# SCH_ELECTROSCOPE_2025-04-18.net
KiCad netlist of a schematic drawn in EasyEDA
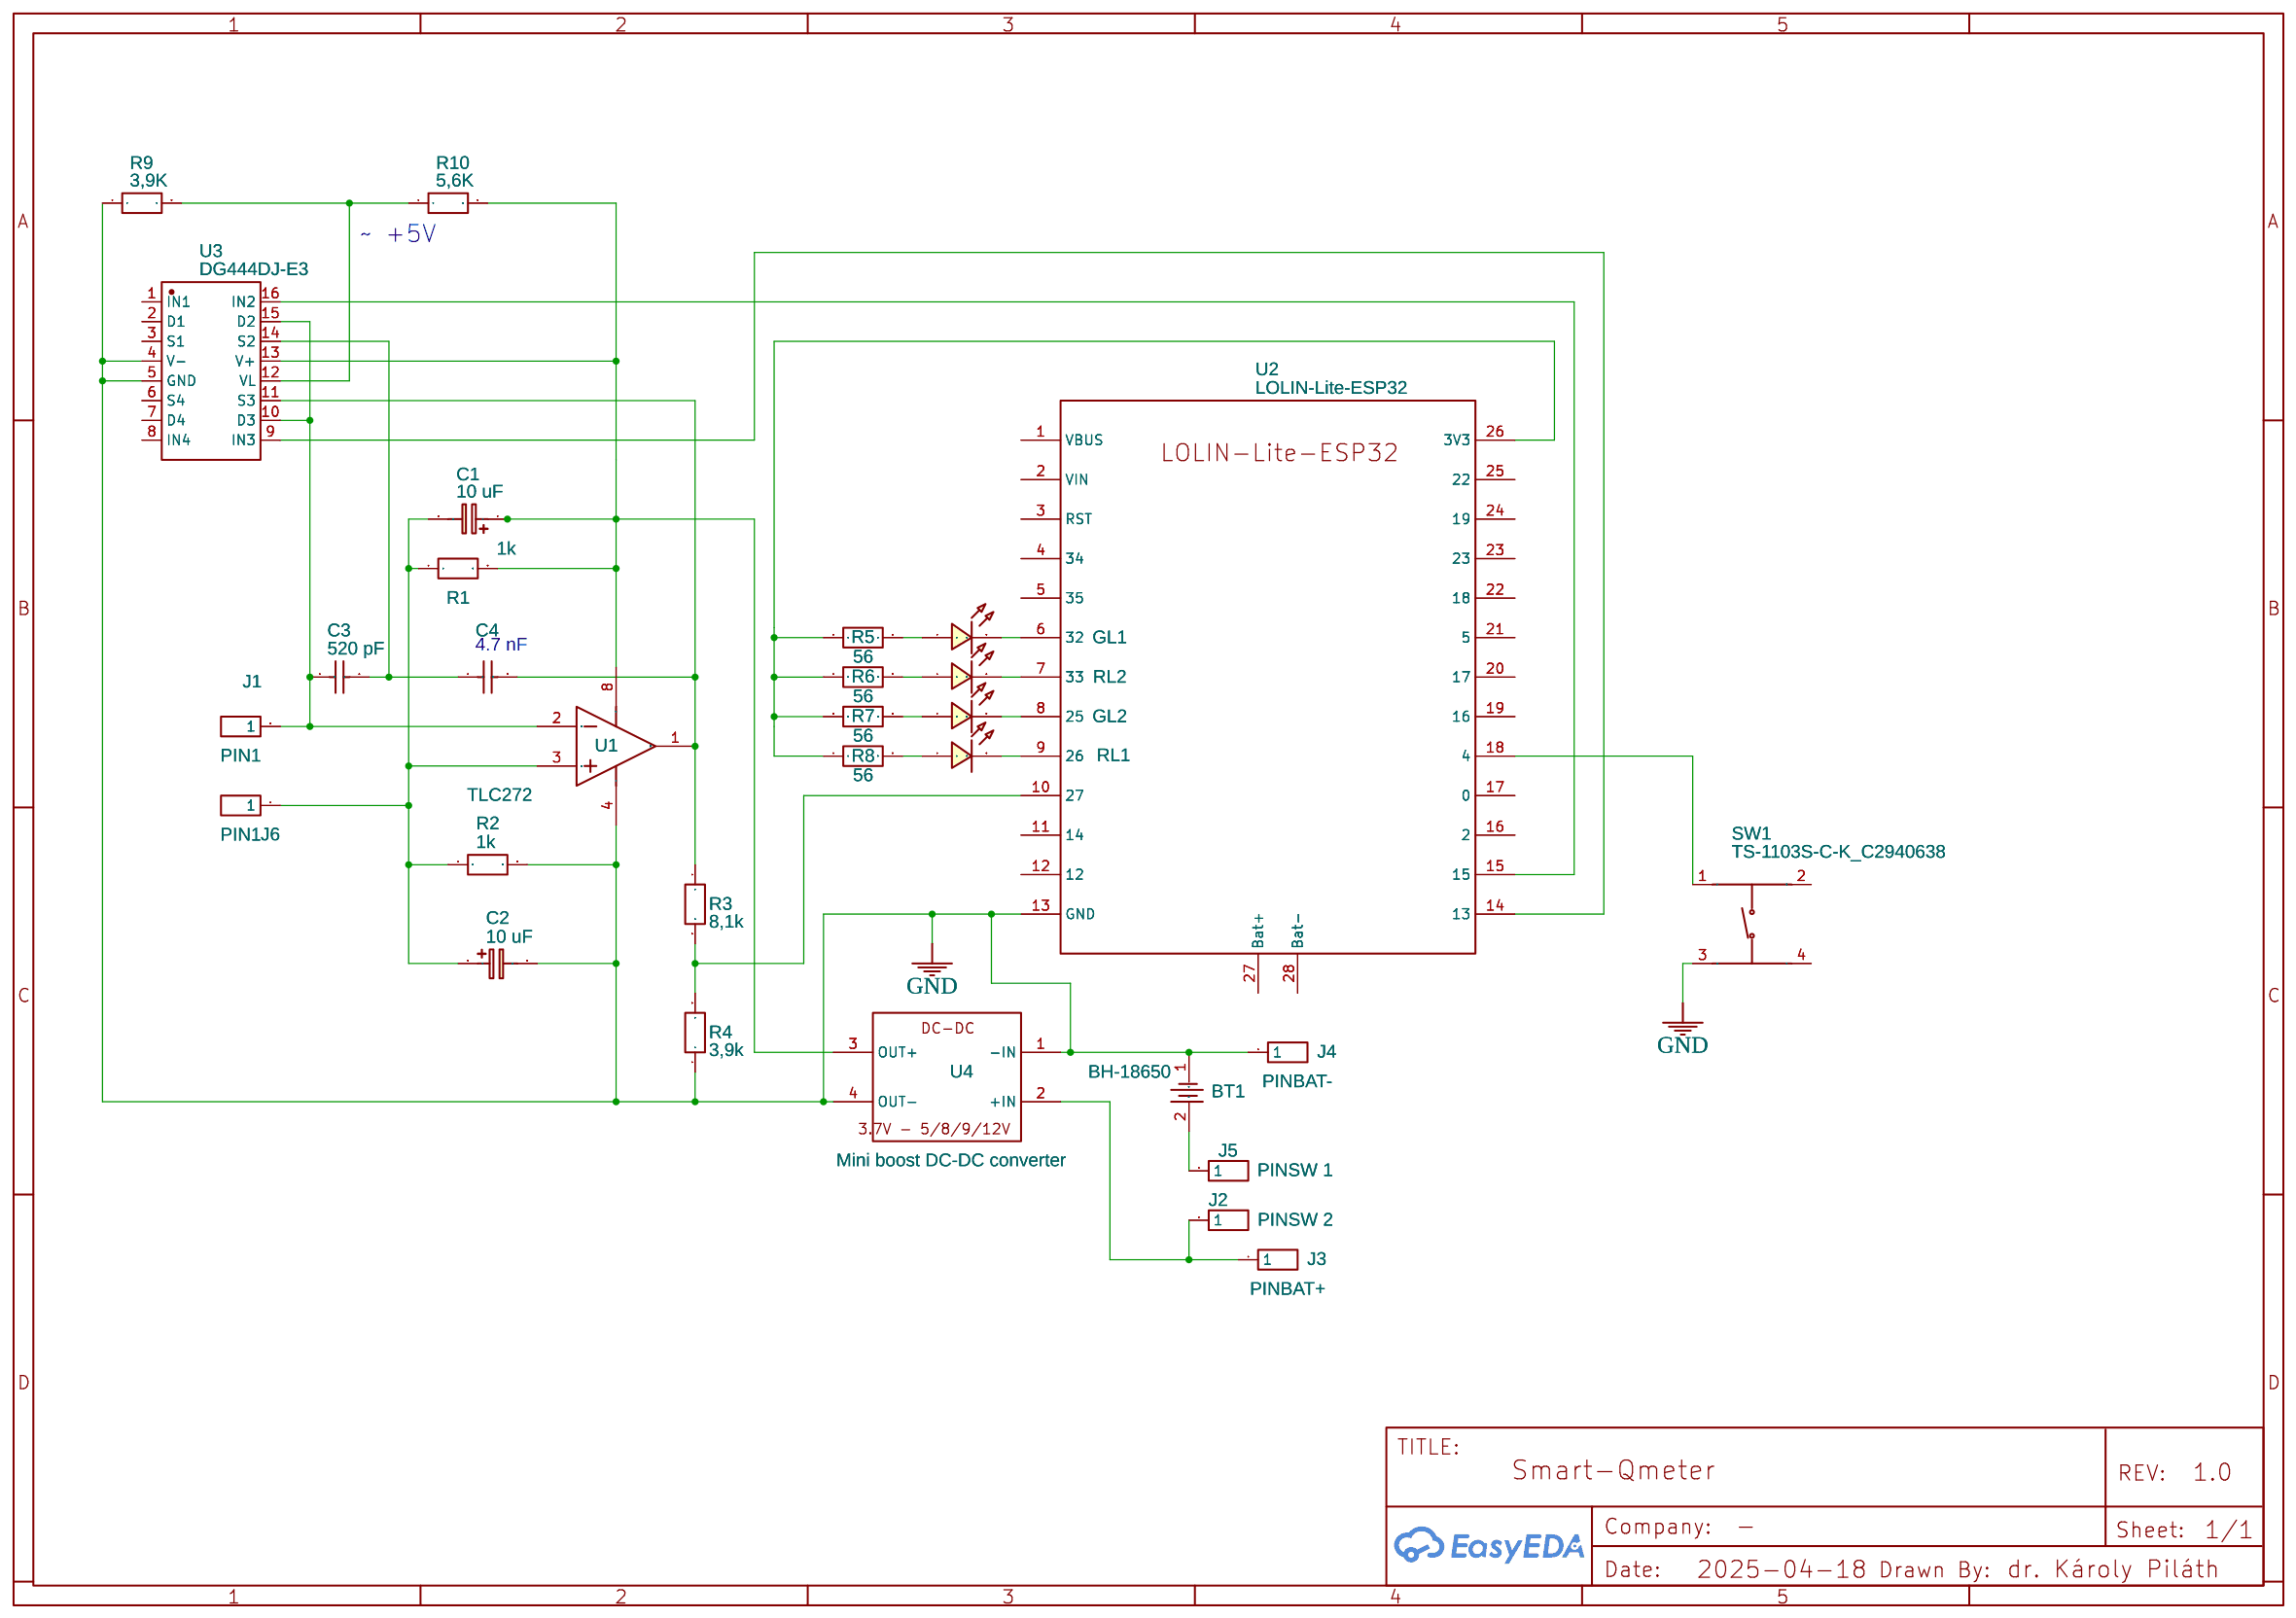
[diagram p0: schematic sheet]

(export (version "E")
  (design (tool "Eeschema 10.0.6"))
  (components
    (comp (ref "BT1")
      (value "BH-18650")
      (fields
        (field (name "Manufacturer Part") "BH-18650-B1BA002")
        (field (name "Manufacturer") "MYOUNG(美阳)")
      )
      (libsource (lib "") (part "BH-18650-B1BA002"))
    )
    (comp (ref "C1") (value "10 uF") (libsource (lib "") (part "CE_TH_D4.0×F1.5_EU")))
    (comp (ref "C2") (value "10 uF") (libsource (lib "") (part "CE_TH_D4.0×F1.5_EU_1")))
    (comp (ref "C3")
      (value "520 pF")
      (fields (field (name "Manufacturer Part") "Capacitor15nf100v") (field (name "Manufacturer") "ReliaPro"))
      (libsource (lib "") (part "CAPACITOR15NF100V"))
    )
    (comp (ref "C4")
      (value "10 nF")
      (fields (field (name "Manufacturer Part") "Capacitor15nf100v") (field (name "Manufacturer") "ReliaPro"))
      (libsource (lib "") (part "CAPACITOR15NF100V"))
    )
    (comp (ref "GL1")
      (value "LED-TH-5mm_R")
      (fields
        (field (name "Manufacturer Part") "333-2SURD/S530-A3")
        (field (name "Manufacturer") "EVERLIGHT(台湾亿光)")
      )
      (libsource (lib "") (part "LED-TH-5mm_R"))
    )
    (comp (ref "GL2")
      (value "LED-TH-5mm_R")
      (fields
        (field (name "Manufacturer Part") "333-2SURD/S530-A3")
        (field (name "Manufacturer") "EVERLIGHT(台湾亿光)")
      )
      (libsource (lib "") (part "LED-TH-5mm_R"))
    )
    (comp (ref "J1") (value "PIN1") (libsource (lib "") (part "HDR-M-2.54_1x1_1")))
    (comp (ref "J2") (value "PINSW 2") (libsource (lib "") (part "HDR-M-2.54_1x1")))
    (comp (ref "J3") (value "PINBAT+") (libsource (lib "") (part "HDR-M-2.54_1x1")))
    (comp (ref "J4") (value "PINBAT-") (libsource (lib "") (part "HDR-M-2.54_1x1")))
    (comp (ref "J5") (value "PINSW 1") (libsource (lib "") (part "HDR-M-2.54_1x1")))
    (comp (ref "J6") (value "PIN1") (libsource (lib "") (part "HDR-M-2.54_1x1_1")))
    (comp (ref "R1") (value "1k") (libsource (lib "") (part "R_AXIAL-0.4_EU")))
    (comp (ref "R2") (value "1k") (libsource (lib "") (part "R_AXIAL-0.4_EU")))
    (comp (ref "R3") (value "8,1k") (libsource (lib "") (part "R_AXIAL-0.4_EU_1")))
    (comp (ref "R4") (value "3,9k") (libsource (lib "") (part "R_AXIAL-0.4_EU_2")))
    (comp (ref "R5") (value "56") (libsource (lib "") (part "R_AXIAL-0.4_EU")))
    (comp (ref "R6") (value "56") (libsource (lib "") (part "R_AXIAL-0.4_EU")))
    (comp (ref "R7") (value "56") (libsource (lib "") (part "R_AXIAL-0.4_EU")))
    (comp (ref "R8") (value "56") (libsource (lib "") (part "R_AXIAL-0.4_EU")))
    (comp (ref "R9") (value "3,9K") (libsource (lib "") (part "R_AXIAL-0.4_EU")))
    (comp (ref "R10") (value "5,6K") (libsource (lib "") (part "R_AXIAL-0.4_EU")))
    (comp (ref "RL1")
      (value "LED-TH-5mm_R")
      (fields
        (field (name "Manufacturer Part") "333-2SURD/S530-A3")
        (field (name "Manufacturer") "EVERLIGHT(台湾亿光)")
      )
      (libsource (lib "") (part "LED-TH-5mm_R_1"))
    )
    (comp (ref "RL2")
      (value "LED-TH-5mm_R")
      (fields
        (field (name "Manufacturer Part") "333-2SURD/S530-A3")
        (field (name "Manufacturer") "EVERLIGHT(台湾亿光)")
      )
      (libsource (lib "") (part "LED-TH-5mm_R_1"))
    )
    (comp (ref "SW1")
      (value "TS-1103S-C-K_C2940638")
      (fields
        (field (name "Manufacturer Part") "TS-1103S-C-K")
        (field (name "Manufacturer") "XKB Connectivity(中国星坤)")
      )
      (libsource (lib "") (part "TS-1103S-C-K_C2940638"))
    )
    (comp (ref "U1")
      (value "TLC272")
      (fields (field (name "Manufacturer Part") "TL062CPE4") (field (name "Manufacturer") "TI(德州仪器)"))
      (libsource (lib "") (part "TL062CPE4"))
    )
    (comp (ref "U2")
      (value "LOLIN-Lite-ESP32")
      (fields (field (name "Manufacturer") "Wemos"))
      (libsource (lib "") (part "LOLIN-Lite-ESP32"))
    )
    (comp (ref "U3")
      (value "DG444DJ-E3")
      (fields (field (name "Manufacturer") "VISHAY(威世)"))
      (libsource (lib "") (part "DG444DJ-E3"))
    )
    (comp (ref "U4")
      (value "Mini boost DC-DC converter")
      (libsource (lib "") (part "Mini boost DC-DC converter"))
    )
  )
  (nets
    (net (code "1") (name "GND") (class "Default")
      (node (ref "BT1") (pin "1") (pinfunction "1_1") (pintype "input"))
      (node (ref "C2") (pin "2") (pinfunction "2_2") (pintype "unspecified"))
      (node (ref "J4") (pin "1") (pinfunction "1_1") (pintype "input"))
      (node (ref "R2") (pin "2") (pinfunction "2_2") (pintype "unspecified"))
      (node (ref "R4") (pin "1") (pinfunction "1_1") (pintype "unspecified"))
      (node (ref "R9") (pin "1") (pinfunction "1_1") (pintype "unspecified"))
      (node (ref "SW1") (pin "3") (pinfunction "3_3") (pintype "unspecified"))
      (node (ref "U1") (pin "4") (pinfunction "V-_4") (pintype "passive"))
      (node (ref "U2") (pin "13") (pinfunction "GND_13") (pintype "unspecified"))
      (node (ref "U3") (pin "4") (pinfunction "V-_4") (pintype "unspecified"))
      (node (ref "U3") (pin "5") (pinfunction "GND_5") (pintype "unspecified"))
      (node (ref "U4") (pin "1") (pinfunction "-IN_1") (pintype "unspecified"))
      (node (ref "U4") (pin "4") (pinfunction "OUT-_4") (pintype "unspecified"))
    )
    (net (code "2") (name "Net-(BT1-Pad2)") (class "Default")
      (node (ref "BT1") (pin "2") (pinfunction "2_2") (pintype "input"))
      (node (ref "J5") (pin "1") (pinfunction "1_1") (pintype "input"))
    )
    (net (code "3") (name "Net-(GL1-Pad1)") (class "Default")
      (node (ref "GL1") (pin "1") (pinfunction "1_1") (pintype "unspecified"))
      (node (ref "R5") (pin "2") (pinfunction "2_2") (pintype "unspecified"))
    )
    (net (code "4") (name "Net-(GL2-Pad1)") (class "Default")
      (node (ref "GL2") (pin "1") (pinfunction "1_1") (pintype "unspecified"))
      (node (ref "R7") (pin "2") (pinfunction "2_2") (pintype "unspecified"))
    )
    (net (code "5") (name "Net-(R6-Pad2)") (class "Default")
      (node (ref "R6") (pin "2") (pinfunction "2_2") (pintype "unspecified"))
      (node (ref "RL2") (pin "1") (pinfunction "1_1") (pintype "unspecified"))
    )
    (net (code "6") (name "Net-(R8-Pad2)") (class "Default")
      (node (ref "R8") (pin "2") (pinfunction "2_2") (pintype "unspecified"))
      (node (ref "RL1") (pin "1") (pinfunction "1_1") (pintype "unspecified"))
    )
    (net (code "7") (name "Net-(U1-INA+)") (class "Default")
      (node (ref "C1") (pin "2") (pinfunction "2_2") (pintype "unspecified"))
      (node (ref "C2") (pin "1") (pinfunction "1_1") (pintype "unspecified"))
      (node (ref "J6") (pin "1") (pinfunction "1_1") (pintype "input"))
      (node (ref "R1") (pin "1") (pinfunction "1_1") (pintype "unspecified"))
      (node (ref "R2") (pin "1") (pinfunction "1_1") (pintype "unspecified"))
      (node (ref "U1") (pin "3") (pinfunction "INA+_3") (pintype "unspecified"))
    )
    (net (code "8") (name "Net-(U1-INA_-)") (class "Default")
      (node (ref "C3") (pin "1") (pinfunction "1_1") (pintype "input"))
      (node (ref "J1") (pin "1") (pinfunction "1_1") (pintype "input"))
      (node (ref "U1") (pin "2") (pinfunction "INA_-_2") (pintype "unspecified"))
      (node (ref "U3") (pin "10") (pinfunction "D3_10") (pintype "unspecified"))
      (node (ref "U3") (pin "15") (pinfunction "D2_15") (pintype "unspecified"))
    )
    (net (code "9") (name "Net-(U1-OUTA)") (class "Default")
      (node (ref "C4") (pin "2") (pinfunction "2_2") (pintype "input"))
      (node (ref "R3") (pin "1") (pinfunction "1_1") (pintype "unspecified"))
      (node (ref "U1") (pin "1") (pinfunction "OUTA_1") (pintype "output"))
      (node (ref "U3") (pin "11") (pinfunction "S3_11") (pintype "unspecified"))
    )
    (net (code "10") (name "Net-(U1-V+)") (class "Default")
      (node (ref "C1") (pin "1") (pinfunction "1_1") (pintype "unspecified"))
      (node (ref "R1") (pin "2") (pinfunction "2_2") (pintype "unspecified"))
      (node (ref "R10") (pin "2") (pinfunction "2_2") (pintype "unspecified"))
      (node (ref "U1") (pin "8") (pinfunction "V+_8") (pintype "passive"))
      (node (ref "U3") (pin "13") (pinfunction "V+_13") (pintype "unspecified"))
      (node (ref "U4") (pin "3") (pinfunction "OUT+_3") (pintype "unspecified"))
    )
    (net (code "11") (name "Net-(U2-3V3)") (class "Default")
      (node (ref "R5") (pin "1") (pinfunction "1_1") (pintype "unspecified"))
      (node (ref "R6") (pin "1") (pinfunction "1_1") (pintype "unspecified"))
      (node (ref "R7") (pin "1") (pinfunction "1_1") (pintype "unspecified"))
      (node (ref "R8") (pin "1") (pinfunction "1_1") (pintype "unspecified"))
      (node (ref "U2") (pin "26") (pinfunction "3V3_26") (pintype "unspecified"))
    )
    (net (code "12") (name "Net-(U2-4)") (class "Default")
      (node (ref "SW1") (pin "1") (pinfunction "1_1") (pintype "unspecified"))
      (node (ref "U2") (pin "18") (pinfunction "4_18") (pintype "unspecified"))
    )
    (net (code "13") (name "Net-(U2-13)") (class "Default")
      (node (ref "U2") (pin "14") (pinfunction "13_14") (pintype "unspecified"))
      (node (ref "U3") (pin "9") (pinfunction "IN3_9") (pintype "unspecified"))
    )
    (net (code "14") (name "Net-(U2-25)") (class "Default")
      (node (ref "GL2") (pin "2") (pinfunction "2_2") (pintype "unspecified"))
      (node (ref "U2") (pin "8") (pinfunction "25_8") (pintype "unspecified"))
    )
    (net (code "15") (name "Net-(U2-26)") (class "Default")
      (node (ref "RL1") (pin "2") (pinfunction "2_2") (pintype "unspecified"))
      (node (ref "U2") (pin "9") (pinfunction "26_9") (pintype "unspecified"))
    )
    (net (code "16") (name "Net-(U2-27)") (class "Default")
      (node (ref "R3") (pin "2") (pinfunction "2_2") (pintype "unspecified"))
      (node (ref "R4") (pin "2") (pinfunction "2_2") (pintype "unspecified"))
      (node (ref "U2") (pin "10") (pinfunction "27_10") (pintype "unspecified"))
    )
    (net (code "17") (name "Net-(U2-32)") (class "Default")
      (node (ref "GL1") (pin "2") (pinfunction "2_2") (pintype "unspecified"))
      (node (ref "U2") (pin "6") (pinfunction "32_6") (pintype "unspecified"))
    )
    (net (code "18") (name "Net-(U2-33)") (class "Default")
      (node (ref "RL2") (pin "2") (pinfunction "2_2") (pintype "unspecified"))
      (node (ref "U2") (pin "7") (pinfunction "33_7") (pintype "unspecified"))
    )
    (net (code "19") (name "Net-(U3-IN2)") (class "Default")
      (node (ref "U2") (pin "15") (pinfunction "15_15") (pintype "unspecified"))
      (node (ref "U3") (pin "16") (pinfunction "IN2_16") (pintype "unspecified"))
    )
    (net (code "20") (name "Net-(U3-S2)") (class "Default")
      (node (ref "C3") (pin "2") (pinfunction "2_2") (pintype "input"))
      (node (ref "C4") (pin "1") (pinfunction "1_1") (pintype "input"))
      (node (ref "U3") (pin "14") (pinfunction "S2_14") (pintype "unspecified"))
    )
    (net (code "21") (name "Net-(U3-VL)") (class "Default")
      (node (ref "R10") (pin "1") (pinfunction "1_1") (pintype "unspecified"))
      (node (ref "R9") (pin "2") (pinfunction "2_2") (pintype "unspecified"))
      (node (ref "U3") (pin "12") (pinfunction "VL_12") (pintype "unspecified"))
    )
    (net (code "22") (name "Net-(U4-+IN)") (class "Default")
      (node (ref "J2") (pin "1") (pinfunction "1_1") (pintype "input"))
      (node (ref "J3") (pin "1") (pinfunction "1_1") (pintype "input"))
      (node (ref "U4") (pin "2") (pinfunction "+IN_2") (pintype "unspecified"))
    )
    (net (code "23") (name "unconnected-(SW1-Pad2)") (class "Default")
      (node (ref "SW1") (pin "2") (pinfunction "2_2") (pintype "unspecified"))
    )
    (net (code "24") (name "unconnected-(SW1-Pad4)") (class "Default")
      (node (ref "SW1") (pin "4") (pinfunction "4_4") (pintype "unspecified"))
    )
    (net (code "25") (name "unconnected-(U2-0-Pad17)") (class "Default")
      (node (ref "U2") (pin "17") (pinfunction "0_17") (pintype "unspecified"))
    )
    (net (code "26") (name "unconnected-(U2-2-Pad16)") (class "Default")
      (node (ref "U2") (pin "16") (pinfunction "2_16") (pintype "unspecified"))
    )
    (net (code "27") (name "unconnected-(U2-5-Pad21)") (class "Default")
      (node (ref "U2") (pin "21") (pinfunction "5_21") (pintype "unspecified"))
    )
    (net (code "28") (name "unconnected-(U2-14-Pad11)") (class "Default")
      (node (ref "U2") (pin "11") (pinfunction "14_11") (pintype "unspecified"))
    )
    (net (code "29") (name "unconnected-(U2-16-Pad19)") (class "Default")
      (node (ref "U2") (pin "19") (pinfunction "16_19") (pintype "unspecified"))
    )
    (net (code "30") (name "unconnected-(U2-17-Pad20)") (class "Default")
      (node (ref "U2") (pin "20") (pinfunction "17_20") (pintype "unspecified"))
    )
    (net (code "31") (name "unconnected-(U2-18-Pad22)") (class "Default")
      (node (ref "U2") (pin "22") (pinfunction "18_22") (pintype "unspecified"))
    )
    (net (code "32") (name "unconnected-(U2-19-Pad24)") (class "Default")
      (node (ref "U2") (pin "24") (pinfunction "19_24") (pintype "unspecified"))
    )
    (net (code "33") (name "unconnected-(U2-22-Pad25)") (class "Default")
      (node (ref "U2") (pin "25") (pinfunction "22_25") (pintype "unspecified"))
    )
    (net (code "34") (name "unconnected-(U2-34-Pad4)") (class "Default")
      (node (ref "U2") (pin "4") (pinfunction "34_4") (pintype "unspecified"))
    )
    (net (code "35") (name "unconnected-(U2-35-Pad5)") (class "Default")
      (node (ref "U2") (pin "5") (pinfunction "35_5") (pintype "unspecified"))
    )
    (net (code "36") (name "unconnected-(U2-Bat+-Pad27)") (class "Default")
      (node (ref "U2") (pin "27") (pinfunction "Bat+_27") (pintype "unspecified"))
    )
    (net (code "37") (name "unconnected-(U2-Bat--Pad28)") (class "Default")
      (node (ref "U2") (pin "28") (pinfunction "Bat-_28") (pintype "unspecified"))
    )
    (net (code "38") (name "unconnected-(U2-Pad12)") (class "Default")
      (node (ref "U2") (pin "12") (pinfunction "12_12") (pintype "unspecified"))
    )
    (net (code "39") (name "unconnected-(U2-Pad23)") (class "Default")
      (node (ref "U2") (pin "23") (pinfunction "23_23") (pintype "unspecified"))
    )
    (net (code "40") (name "unconnected-(U2-RST-Pad3)") (class "Default")
      (node (ref "U2") (pin "3") (pinfunction "RST_3") (pintype "unspecified"))
    )
    (net (code "41") (name "unconnected-(U2-VBUS-Pad1)") (class "Default")
      (node (ref "U2") (pin "1") (pinfunction "VBUS_1") (pintype "unspecified"))
    )
    (net (code "42") (name "unconnected-(U2-VIN-Pad2)") (class "Default")
      (node (ref "U2") (pin "2") (pinfunction "VIN_2") (pintype "unspecified"))
    )
    (net (code "43") (name "unconnected-(U3-D1-Pad2)") (class "Default")
      (node (ref "U3") (pin "2") (pinfunction "D1_2") (pintype "unspecified"))
    )
    (net (code "44") (name "unconnected-(U3-D4-Pad7)") (class "Default")
      (node (ref "U3") (pin "7") (pinfunction "D4_7") (pintype "unspecified"))
    )
    (net (code "45") (name "unconnected-(U3-IN1-Pad1)") (class "Default")
      (node (ref "U3") (pin "1") (pinfunction "IN1_1") (pintype "unspecified"))
    )
    (net (code "46") (name "unconnected-(U3-IN4-Pad8)") (class "Default")
      (node (ref "U3") (pin "8") (pinfunction "IN4_8") (pintype "unspecified"))
    )
    (net (code "47") (name "unconnected-(U3-S1-Pad3)") (class "Default")
      (node (ref "U3") (pin "3") (pinfunction "S1_3") (pintype "unspecified"))
    )
    (net (code "48") (name "unconnected-(U3-S4-Pad6)") (class "Default")
      (node (ref "U3") (pin "6") (pinfunction "S4_6") (pintype "unspecified"))
    )
  )
)
